# untitled.net
KiCad netlist of a schematic drawn in EAGLE
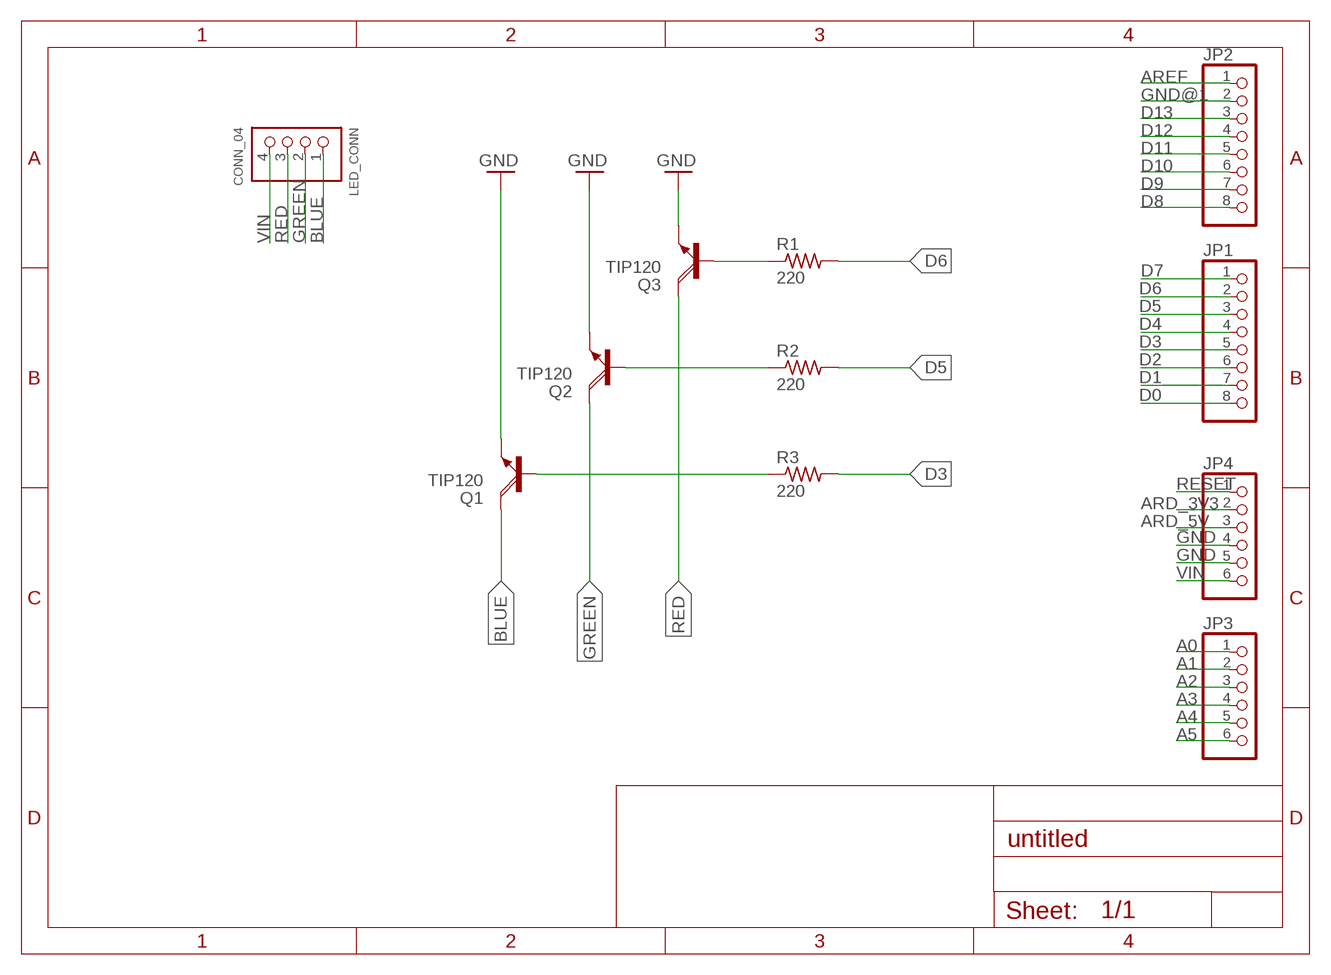
[diagram p0: schematic, sheet 1]

(export (version "E")
  (design (tool "Eeschema 10.0.6"))
  (components
    (comp (ref "JP1")
      (value "PINHD-1X8")
      (footprint "eagle-import:1X08")
      (libsource (lib "eagle-import") (part "PINHD-1X8"))
    )
    (comp (ref "JP2")
      (value "PINHD-1X8")
      (footprint "eagle-import:1X08")
      (libsource (lib "eagle-import") (part "PINHD-1X8"))
    )
    (comp (ref "JP3")
      (value "PINHD-1X6")
      (footprint "eagle-import:1X06")
      (libsource (lib "eagle-import") (part "PINHD-1X6"))
    )
    (comp (ref "JP4")
      (value "PINHD-1X6")
      (footprint "eagle-import:1X06")
      (libsource (lib "eagle-import") (part "PINHD-1X6"))
    )
    (comp (ref "LED_CONN")
      (value "CONN_04")
      (footprint "eagle-import:SCREWTERMINAL-5MM-4")
      (libsource (lib "eagle-import") (part "CONN_04"))
    )
    (comp (ref "Q1")
      (value "TIP120")
      (footprint "eagle-import:TO220AH")
      (libsource (lib "eagle-import") (part "TIP120"))
    )
    (comp (ref "Q2")
      (value "TIP120")
      (footprint "eagle-import:TO220AH")
      (libsource (lib "eagle-import") (part "TIP120"))
    )
    (comp (ref "Q3")
      (value "TIP120")
      (footprint "eagle-import:TO220AH")
      (libsource (lib "eagle-import") (part "TIP120"))
    )
    (comp (ref "R1")
      (value "220")
      (footprint "eagle-import:0207_10")
      (libsource (lib "eagle-import") (part "R-US_0207/10"))
    )
    (comp (ref "R2")
      (value "220")
      (footprint "eagle-import:0207_10")
      (libsource (lib "eagle-import") (part "R-US_0207/10"))
    )
    (comp (ref "R3")
      (value "220")
      (footprint "eagle-import:0207_10")
      (libsource (lib "eagle-import") (part "R-US_0207/10"))
    )
  )
  (nets
    (net (code "1") (name "/A0") (class "Default")
      (node (ref "JP3") (pin "1") (pinfunction "1_1") (pintype "passive"))
    )
    (net (code "2") (name "/A1") (class "Default")
      (node (ref "JP3") (pin "2") (pinfunction "2_2") (pintype "passive"))
    )
    (net (code "3") (name "/A2") (class "Default")
      (node (ref "JP3") (pin "3") (pinfunction "3_3") (pintype "passive"))
    )
    (net (code "4") (name "/A3") (class "Default")
      (node (ref "JP3") (pin "4") (pinfunction "4_4") (pintype "passive"))
    )
    (net (code "5") (name "/A4") (class "Default")
      (node (ref "JP3") (pin "5") (pinfunction "5_5") (pintype "passive"))
    )
    (net (code "6") (name "/A5") (class "Default")
      (node (ref "JP3") (pin "6") (pinfunction "6_6") (pintype "passive"))
    )
    (net (code "7") (name "/ARD_3V3") (class "Default")
      (node (ref "JP4") (pin "2") (pinfunction "2_2") (pintype "passive"))
    )
    (net (code "8") (name "/ARD_5V") (class "Default")
      (node (ref "JP4") (pin "3") (pinfunction "3_3") (pintype "passive"))
    )
    (net (code "9") (name "/AREF") (class "Default")
      (node (ref "JP2") (pin "1") (pinfunction "1_1") (pintype "passive"))
    )
    (net (code "10") (name "/D0") (class "Default")
      (node (ref "JP1") (pin "8") (pinfunction "8_8") (pintype "passive"))
    )
    (net (code "11") (name "/D1") (class "Default")
      (node (ref "JP1") (pin "7") (pinfunction "7_7") (pintype "passive"))
    )
    (net (code "12") (name "/D2") (class "Default")
      (node (ref "JP1") (pin "6") (pinfunction "6_6") (pintype "passive"))
    )
    (net (code "13") (name "/D4") (class "Default")
      (node (ref "JP1") (pin "4") (pinfunction "4_4") (pintype "passive"))
    )
    (net (code "14") (name "/D7") (class "Default")
      (node (ref "JP1") (pin "1") (pinfunction "1_1") (pintype "passive"))
    )
    (net (code "15") (name "/D8") (class "Default")
      (node (ref "JP2") (pin "8") (pinfunction "8_8") (pintype "passive"))
    )
    (net (code "16") (name "/D9") (class "Default")
      (node (ref "JP2") (pin "7") (pinfunction "7_7") (pintype "passive"))
    )
    (net (code "17") (name "/D10") (class "Default")
      (node (ref "JP2") (pin "6") (pinfunction "6_6") (pintype "passive"))
    )
    (net (code "18") (name "/D11") (class "Default")
      (node (ref "JP2") (pin "5") (pinfunction "5_5") (pintype "passive"))
    )
    (net (code "19") (name "/D12") (class "Default")
      (node (ref "JP2") (pin "4") (pinfunction "4_4") (pintype "passive"))
    )
    (net (code "20") (name "/D13") (class "Default")
      (node (ref "JP2") (pin "3") (pinfunction "3_3") (pintype "passive"))
    )
    (net (code "21") (name "/GND@1") (class "Default")
      (node (ref "JP2") (pin "2") (pinfunction "2_2") (pintype "passive"))
    )
    (net (code "22") (name "/RESET") (class "Default")
      (node (ref "JP4") (pin "1") (pinfunction "1_1") (pintype "passive"))
    )
    (net (code "23") (name "/VIN") (class "Default")
      (node (ref "JP4") (pin "6") (pinfunction "6_6") (pintype "passive"))
      (node (ref "LED_CONN") (pin "4") (pinfunction "4_4") (pintype "bidirectional"))
    )
    (net (code "24") (name "BLUE") (class "Default")
      (node (ref "LED_CONN") (pin "1") (pinfunction "1_1") (pintype "bidirectional"))
      (node (ref "Q1") (pin "C") (pinfunction "C_C") (pintype "passive"))
    )
    (net (code "25") (name "D3") (class "Default")
      (node (ref "JP1") (pin "5") (pinfunction "5_5") (pintype "passive"))
      (node (ref "R3") (pin "2") (pinfunction "2_2") (pintype "passive"))
    )
    (net (code "26") (name "D5") (class "Default")
      (node (ref "JP1") (pin "3") (pinfunction "3_3") (pintype "passive"))
      (node (ref "R2") (pin "2") (pinfunction "2_2") (pintype "passive"))
    )
    (net (code "27") (name "D6") (class "Default")
      (node (ref "JP1") (pin "2") (pinfunction "2_2") (pintype "passive"))
      (node (ref "R1") (pin "2") (pinfunction "2_2") (pintype "passive"))
    )
    (net (code "28") (name "GND") (class "Default")
      (node (ref "JP4") (pin "4") (pinfunction "4_4") (pintype "passive"))
      (node (ref "JP4") (pin "5") (pinfunction "5_5") (pintype "passive"))
      (node (ref "Q1") (pin "E") (pinfunction "E_E") (pintype "passive"))
      (node (ref "Q2") (pin "E") (pinfunction "E_E") (pintype "passive"))
      (node (ref "Q3") (pin "E") (pinfunction "E_E") (pintype "passive"))
    )
    (net (code "29") (name "GREEN") (class "Default")
      (node (ref "LED_CONN") (pin "2") (pinfunction "2_2") (pintype "bidirectional"))
      (node (ref "Q2") (pin "C") (pinfunction "C_C") (pintype "passive"))
    )
    (net (code "30") (name "Net-(Q1-PadB)") (class "Default")
      (node (ref "Q1") (pin "B") (pinfunction "B_B") (pintype "passive"))
      (node (ref "R3") (pin "1") (pinfunction "1_1") (pintype "passive"))
    )
    (net (code "31") (name "Net-(Q2-PadB)") (class "Default")
      (node (ref "Q2") (pin "B") (pinfunction "B_B") (pintype "passive"))
      (node (ref "R2") (pin "1") (pinfunction "1_1") (pintype "passive"))
    )
    (net (code "32") (name "Net-(Q3-PadB)") (class "Default")
      (node (ref "Q3") (pin "B") (pinfunction "B_B") (pintype "passive"))
      (node (ref "R1") (pin "1") (pinfunction "1_1") (pintype "passive"))
    )
    (net (code "33") (name "RED") (class "Default")
      (node (ref "LED_CONN") (pin "3") (pinfunction "3_3") (pintype "bidirectional"))
      (node (ref "Q3") (pin "C") (pinfunction "C_C") (pintype "passive"))
    )
  )
)
